# LED_Board.net
KiCad netlist of a schematic drawn in EAGLE
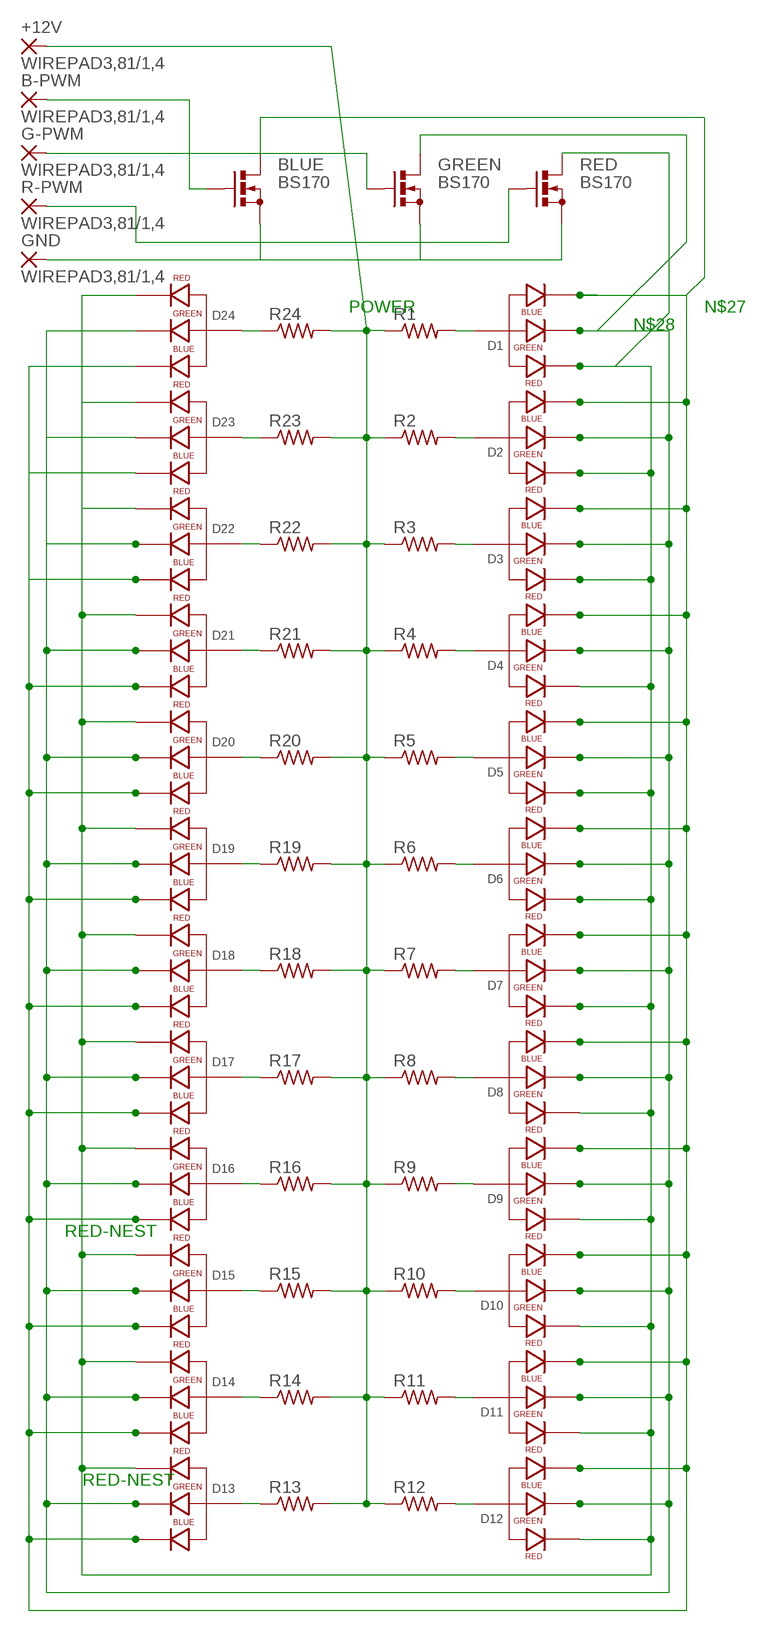
[diagram p0: schematic, sheet 1]

(export (version "E")
  (design (tool "Eeschema 10.0.6"))
  (components
    (comp (ref "+12V")
      (value "WIREPAD3,81/1,4")
      (footprint "eagle-import:3,81_1,4")
      (libsource (lib "eagle-import") (part "WIREPAD3,81/1,4"))
    )
    (comp (ref "B-PWM")
      (value "WIREPAD3,81/1,4")
      (footprint "eagle-import:3,81_1,4")
      (libsource (lib "eagle-import") (part "WIREPAD3,81/1,4"))
    )
    (comp (ref "BLUE")
      (value "BS170")
      (footprint "eagle-import:SOT54E")
      (libsource (lib "eagle-import") (part "BS170"))
    )
    (comp (ref "D1")
      (value "LED-RGB-CA-THRUCLEAR")
      (footprint "eagle-import:LED-RGB-THRU")
      (libsource (lib "eagle-import") (part "LED-RGB-CA-THRUCLEAR"))
    )
    (comp (ref "D2")
      (value "LED-RGB-CA-THRUCLEAR")
      (footprint "eagle-import:LED-RGB-THRU")
      (libsource (lib "eagle-import") (part "LED-RGB-CA-THRUCLEAR"))
    )
    (comp (ref "D3")
      (value "LED-RGB-CA-THRUCLEAR")
      (footprint "eagle-import:LED-RGB-THRU")
      (libsource (lib "eagle-import") (part "LED-RGB-CA-THRUCLEAR"))
    )
    (comp (ref "D4")
      (value "LED-RGB-CA-THRUCLEAR")
      (footprint "eagle-import:LED-RGB-THRU")
      (libsource (lib "eagle-import") (part "LED-RGB-CA-THRUCLEAR"))
    )
    (comp (ref "D5")
      (value "LED-RGB-CA-THRUCLEAR")
      (footprint "eagle-import:LED-RGB-THRU")
      (libsource (lib "eagle-import") (part "LED-RGB-CA-THRUCLEAR"))
    )
    (comp (ref "D6")
      (value "LED-RGB-CA-THRUCLEAR")
      (footprint "eagle-import:LED-RGB-THRU")
      (libsource (lib "eagle-import") (part "LED-RGB-CA-THRUCLEAR"))
    )
    (comp (ref "D7")
      (value "LED-RGB-CA-THRUCLEAR")
      (footprint "eagle-import:LED-RGB-THRU")
      (libsource (lib "eagle-import") (part "LED-RGB-CA-THRUCLEAR"))
    )
    (comp (ref "D8")
      (value "LED-RGB-CA-THRUCLEAR")
      (footprint "eagle-import:LED-RGB-THRU")
      (libsource (lib "eagle-import") (part "LED-RGB-CA-THRUCLEAR"))
    )
    (comp (ref "D9")
      (value "LED-RGB-CA-THRUCLEAR")
      (footprint "eagle-import:LED-RGB-THRU")
      (libsource (lib "eagle-import") (part "LED-RGB-CA-THRUCLEAR"))
    )
    (comp (ref "D10")
      (value "LED-RGB-CA-THRUCLEAR")
      (footprint "eagle-import:LED-RGB-THRU")
      (libsource (lib "eagle-import") (part "LED-RGB-CA-THRUCLEAR"))
    )
    (comp (ref "D11")
      (value "LED-RGB-CA-THRUCLEAR")
      (footprint "eagle-import:LED-RGB-THRU")
      (libsource (lib "eagle-import") (part "LED-RGB-CA-THRUCLEAR"))
    )
    (comp (ref "D12")
      (value "LED-RGB-CA-THRUCLEAR")
      (footprint "eagle-import:LED-RGB-THRU")
      (libsource (lib "eagle-import") (part "LED-RGB-CA-THRUCLEAR"))
    )
    (comp (ref "D13")
      (value "LED-RGB-CA-THRUCLEAR")
      (footprint "eagle-import:LED-RGB-THRU")
      (libsource (lib "eagle-import") (part "LED-RGB-CA-THRUCLEAR"))
    )
    (comp (ref "D14")
      (value "LED-RGB-CA-THRUCLEAR")
      (footprint "eagle-import:LED-RGB-THRU")
      (libsource (lib "eagle-import") (part "LED-RGB-CA-THRUCLEAR"))
    )
    (comp (ref "D15")
      (value "LED-RGB-CA-THRUCLEAR")
      (footprint "eagle-import:LED-RGB-THRU")
      (libsource (lib "eagle-import") (part "LED-RGB-CA-THRUCLEAR"))
    )
    (comp (ref "D16")
      (value "LED-RGB-CA-THRUCLEAR")
      (footprint "eagle-import:LED-RGB-THRU")
      (libsource (lib "eagle-import") (part "LED-RGB-CA-THRUCLEAR"))
    )
    (comp (ref "D17")
      (value "LED-RGB-CA-THRUCLEAR")
      (footprint "eagle-import:LED-RGB-THRU")
      (libsource (lib "eagle-import") (part "LED-RGB-CA-THRUCLEAR"))
    )
    (comp (ref "D18")
      (value "LED-RGB-CA-THRUCLEAR")
      (footprint "eagle-import:LED-RGB-THRU")
      (libsource (lib "eagle-import") (part "LED-RGB-CA-THRUCLEAR"))
    )
    (comp (ref "D19")
      (value "LED-RGB-CA-THRUCLEAR")
      (footprint "eagle-import:LED-RGB-THRU")
      (libsource (lib "eagle-import") (part "LED-RGB-CA-THRUCLEAR"))
    )
    (comp (ref "D20")
      (value "LED-RGB-CA-THRUCLEAR")
      (footprint "eagle-import:LED-RGB-THRU")
      (libsource (lib "eagle-import") (part "LED-RGB-CA-THRUCLEAR"))
    )
    (comp (ref "D21")
      (value "LED-RGB-CA-THRUCLEAR")
      (footprint "eagle-import:LED-RGB-THRU")
      (libsource (lib "eagle-import") (part "LED-RGB-CA-THRUCLEAR"))
    )
    (comp (ref "D22")
      (value "LED-RGB-CA-THRUCLEAR")
      (footprint "eagle-import:LED-RGB-THRU")
      (libsource (lib "eagle-import") (part "LED-RGB-CA-THRUCLEAR"))
    )
    (comp (ref "D23")
      (value "LED-RGB-CA-THRUCLEAR")
      (footprint "eagle-import:LED-RGB-THRU")
      (libsource (lib "eagle-import") (part "LED-RGB-CA-THRUCLEAR"))
    )
    (comp (ref "D24")
      (value "LED-RGB-CA-THRUCLEAR")
      (footprint "eagle-import:LED-RGB-THRU")
      (libsource (lib "eagle-import") (part "LED-RGB-CA-THRUCLEAR"))
    )
    (comp (ref "G-PWM")
      (value "WIREPAD3,81/1,4")
      (footprint "eagle-import:3,81_1,4")
      (libsource (lib "eagle-import") (part "WIREPAD3,81/1,4"))
    )
    (comp (ref "GND")
      (value "WIREPAD3,81/1,4")
      (footprint "eagle-import:3,81_1,4")
      (libsource (lib "eagle-import") (part "WIREPAD3,81/1,4"))
    )
    (comp (ref "GREEN")
      (value "BS170")
      (footprint "eagle-import:SOT54E")
      (libsource (lib "eagle-import") (part "BS170"))
    )
    (comp (ref "R-PWM")
      (value "WIREPAD3,81/1,4")
      (footprint "eagle-import:3,81_1,4")
      (libsource (lib "eagle-import") (part "WIREPAD3,81/1,4"))
    )
    (comp (ref "R1")
      (value "R-US_0207/10")
      (footprint "eagle-import:0207_10")
      (libsource (lib "eagle-import") (part "R-US_0207/10"))
    )
    (comp (ref "R2")
      (value "R-US_0207/10")
      (footprint "eagle-import:0207_10")
      (libsource (lib "eagle-import") (part "R-US_0207/10"))
    )
    (comp (ref "R3")
      (value "R-US_0207/10")
      (footprint "eagle-import:0207_10")
      (libsource (lib "eagle-import") (part "R-US_0207/10"))
    )
    (comp (ref "R4")
      (value "R-US_0207/10")
      (footprint "eagle-import:0207_10")
      (libsource (lib "eagle-import") (part "R-US_0207/10"))
    )
    (comp (ref "R5")
      (value "R-US_0207/10")
      (footprint "eagle-import:0207_10")
      (libsource (lib "eagle-import") (part "R-US_0207/10"))
    )
    (comp (ref "R6")
      (value "R-US_0207/10")
      (footprint "eagle-import:0207_10")
      (libsource (lib "eagle-import") (part "R-US_0207/10"))
    )
    (comp (ref "R7")
      (value "R-US_0207/10")
      (footprint "eagle-import:0207_10")
      (libsource (lib "eagle-import") (part "R-US_0207/10"))
    )
    (comp (ref "R8")
      (value "R-US_0207/10")
      (footprint "eagle-import:0207_10")
      (libsource (lib "eagle-import") (part "R-US_0207/10"))
    )
    (comp (ref "R9")
      (value "R-US_0207/10")
      (footprint "eagle-import:0207_10")
      (libsource (lib "eagle-import") (part "R-US_0207/10"))
    )
    (comp (ref "R10")
      (value "R-US_0207/10")
      (footprint "eagle-import:0207_10")
      (libsource (lib "eagle-import") (part "R-US_0207/10"))
    )
    (comp (ref "R11")
      (value "R-US_0207/10")
      (footprint "eagle-import:0207_10")
      (libsource (lib "eagle-import") (part "R-US_0207/10"))
    )
    (comp (ref "R12")
      (value "R-US_0207/10")
      (footprint "eagle-import:0207_10")
      (libsource (lib "eagle-import") (part "R-US_0207/10"))
    )
    (comp (ref "R13")
      (value "R-US_0207/10")
      (footprint "eagle-import:0207_10")
      (libsource (lib "eagle-import") (part "R-US_0207/10"))
    )
    (comp (ref "R14")
      (value "R-US_0207/10")
      (footprint "eagle-import:0207_10")
      (libsource (lib "eagle-import") (part "R-US_0207/10"))
    )
    (comp (ref "R15")
      (value "R-US_0207/10")
      (footprint "eagle-import:0207_10")
      (libsource (lib "eagle-import") (part "R-US_0207/10"))
    )
    (comp (ref "R16")
      (value "R-US_0207/10")
      (footprint "eagle-import:0207_10")
      (libsource (lib "eagle-import") (part "R-US_0207/10"))
    )
    (comp (ref "R17")
      (value "R-US_0207/10")
      (footprint "eagle-import:0207_10")
      (libsource (lib "eagle-import") (part "R-US_0207/10"))
    )
    (comp (ref "R18")
      (value "R-US_0207/10")
      (footprint "eagle-import:0207_10")
      (libsource (lib "eagle-import") (part "R-US_0207/10"))
    )
    (comp (ref "R19")
      (value "R-US_0207/10")
      (footprint "eagle-import:0207_10")
      (libsource (lib "eagle-import") (part "R-US_0207/10"))
    )
    (comp (ref "R20")
      (value "R-US_0207/10")
      (footprint "eagle-import:0207_10")
      (libsource (lib "eagle-import") (part "R-US_0207/10"))
    )
    (comp (ref "R21")
      (value "R-US_0207/10")
      (footprint "eagle-import:0207_10")
      (libsource (lib "eagle-import") (part "R-US_0207/10"))
    )
    (comp (ref "R22")
      (value "R-US_0207/10")
      (footprint "eagle-import:0207_10")
      (libsource (lib "eagle-import") (part "R-US_0207/10"))
    )
    (comp (ref "R23")
      (value "R-US_0207/10")
      (footprint "eagle-import:0207_10")
      (libsource (lib "eagle-import") (part "R-US_0207/10"))
    )
    (comp (ref "R24")
      (value "R-US_0207/10")
      (footprint "eagle-import:0207_10")
      (libsource (lib "eagle-import") (part "R-US_0207/10"))
    )
    (comp (ref "RED")
      (value "BS170")
      (footprint "eagle-import:SOT54E")
      (libsource (lib "eagle-import") (part "BS170"))
    )
  )
  (nets
    (net (code "1") (name "/N$27") (class "Default")
      (node (ref "BLUE") (pin "D") (pinfunction "D_D") (pintype "passive"))
      (node (ref "D1") (pin "4") (pinfunction "BLUE_CATHODE_4") (pintype "bidirectional"))
      (node (ref "D10") (pin "4") (pinfunction "BLUE_CATHODE_4") (pintype "bidirectional"))
      (node (ref "D11") (pin "4") (pinfunction "BLUE_CATHODE_4") (pintype "bidirectional"))
      (node (ref "D12") (pin "4") (pinfunction "BLUE_CATHODE_4") (pintype "bidirectional"))
      (node (ref "D13") (pin "4") (pinfunction "BLUE_CATHODE_4") (pintype "bidirectional"))
      (node (ref "D14") (pin "4") (pinfunction "BLUE_CATHODE_4") (pintype "bidirectional"))
      (node (ref "D15") (pin "4") (pinfunction "BLUE_CATHODE_4") (pintype "bidirectional"))
      (node (ref "D16") (pin "4") (pinfunction "BLUE_CATHODE_4") (pintype "bidirectional"))
      (node (ref "D17") (pin "4") (pinfunction "BLUE_CATHODE_4") (pintype "bidirectional"))
      (node (ref "D18") (pin "4") (pinfunction "BLUE_CATHODE_4") (pintype "bidirectional"))
      (node (ref "D19") (pin "4") (pinfunction "BLUE_CATHODE_4") (pintype "bidirectional"))
      (node (ref "D2") (pin "4") (pinfunction "BLUE_CATHODE_4") (pintype "bidirectional"))
      (node (ref "D20") (pin "4") (pinfunction "BLUE_CATHODE_4") (pintype "bidirectional"))
      (node (ref "D21") (pin "4") (pinfunction "BLUE_CATHODE_4") (pintype "bidirectional"))
      (node (ref "D22") (pin "4") (pinfunction "BLUE_CATHODE_4") (pintype "bidirectional"))
      (node (ref "D23") (pin "4") (pinfunction "BLUE_CATHODE_4") (pintype "bidirectional"))
      (node (ref "D24") (pin "4") (pinfunction "BLUE_CATHODE_4") (pintype "bidirectional"))
      (node (ref "D3") (pin "4") (pinfunction "BLUE_CATHODE_4") (pintype "bidirectional"))
      (node (ref "D4") (pin "4") (pinfunction "BLUE_CATHODE_4") (pintype "bidirectional"))
      (node (ref "D5") (pin "4") (pinfunction "BLUE_CATHODE_4") (pintype "bidirectional"))
      (node (ref "D6") (pin "4") (pinfunction "BLUE_CATHODE_4") (pintype "bidirectional"))
      (node (ref "D7") (pin "4") (pinfunction "BLUE_CATHODE_4") (pintype "bidirectional"))
      (node (ref "D8") (pin "4") (pinfunction "BLUE_CATHODE_4") (pintype "bidirectional"))
      (node (ref "D9") (pin "4") (pinfunction "BLUE_CATHODE_4") (pintype "bidirectional"))
    )
    (net (code "2") (name "/N$28") (class "Default")
      (node (ref "D1") (pin "3") (pinfunction "GREEN_CATHODE_3") (pintype "bidirectional"))
      (node (ref "D10") (pin "3") (pinfunction "GREEN_CATHODE_3") (pintype "bidirectional"))
      (node (ref "D11") (pin "3") (pinfunction "GREEN_CATHODE_3") (pintype "bidirectional"))
      (node (ref "D12") (pin "3") (pinfunction "GREEN_CATHODE_3") (pintype "bidirectional"))
      (node (ref "D13") (pin "3") (pinfunction "GREEN_CATHODE_3") (pintype "bidirectional"))
      (node (ref "D14") (pin "3") (pinfunction "GREEN_CATHODE_3") (pintype "bidirectional"))
      (node (ref "D15") (pin "3") (pinfunction "GREEN_CATHODE_3") (pintype "bidirectional"))
      (node (ref "D16") (pin "3") (pinfunction "GREEN_CATHODE_3") (pintype "bidirectional"))
      (node (ref "D17") (pin "3") (pinfunction "GREEN_CATHODE_3") (pintype "bidirectional"))
      (node (ref "D18") (pin "3") (pinfunction "GREEN_CATHODE_3") (pintype "bidirectional"))
      (node (ref "D19") (pin "3") (pinfunction "GREEN_CATHODE_3") (pintype "bidirectional"))
      (node (ref "D2") (pin "3") (pinfunction "GREEN_CATHODE_3") (pintype "bidirectional"))
      (node (ref "D20") (pin "3") (pinfunction "GREEN_CATHODE_3") (pintype "bidirectional"))
      (node (ref "D21") (pin "3") (pinfunction "GREEN_CATHODE_3") (pintype "bidirectional"))
      (node (ref "D22") (pin "3") (pinfunction "GREEN_CATHODE_3") (pintype "bidirectional"))
      (node (ref "D23") (pin "3") (pinfunction "GREEN_CATHODE_3") (pintype "bidirectional"))
      (node (ref "D24") (pin "3") (pinfunction "GREEN_CATHODE_3") (pintype "bidirectional"))
      (node (ref "D3") (pin "3") (pinfunction "GREEN_CATHODE_3") (pintype "bidirectional"))
      (node (ref "D4") (pin "3") (pinfunction "GREEN_CATHODE_3") (pintype "bidirectional"))
      (node (ref "D5") (pin "3") (pinfunction "GREEN_CATHODE_3") (pintype "bidirectional"))
      (node (ref "D6") (pin "3") (pinfunction "GREEN_CATHODE_3") (pintype "bidirectional"))
      (node (ref "D7") (pin "3") (pinfunction "GREEN_CATHODE_3") (pintype "bidirectional"))
      (node (ref "D8") (pin "3") (pinfunction "GREEN_CATHODE_3") (pintype "bidirectional"))
      (node (ref "D9") (pin "3") (pinfunction "GREEN_CATHODE_3") (pintype "bidirectional"))
      (node (ref "GREEN") (pin "D") (pinfunction "D_D") (pintype "passive"))
    )
    (net (code "3") (name "/POWER") (class "Default")
      (node (ref "+12V") (pin "1") (pinfunction "P_1") (pintype "passive"))
      (node (ref "R1") (pin "1") (pinfunction "1_1") (pintype "passive"))
      (node (ref "R10") (pin "1") (pinfunction "1_1") (pintype "passive"))
      (node (ref "R11") (pin "1") (pinfunction "1_1") (pintype "passive"))
      (node (ref "R12") (pin "1") (pinfunction "1_1") (pintype "passive"))
      (node (ref "R13") (pin "2") (pinfunction "2_2") (pintype "passive"))
      (node (ref "R14") (pin "2") (pinfunction "2_2") (pintype "passive"))
      (node (ref "R15") (pin "2") (pinfunction "2_2") (pintype "passive"))
      (node (ref "R16") (pin "2") (pinfunction "2_2") (pintype "passive"))
      (node (ref "R17") (pin "2") (pinfunction "2_2") (pintype "passive"))
      (node (ref "R18") (pin "2") (pinfunction "2_2") (pintype "passive"))
      (node (ref "R19") (pin "2") (pinfunction "2_2") (pintype "passive"))
      (node (ref "R2") (pin "1") (pinfunction "1_1") (pintype "passive"))
      (node (ref "R20") (pin "2") (pinfunction "2_2") (pintype "passive"))
      (node (ref "R21") (pin "2") (pinfunction "2_2") (pintype "passive"))
      (node (ref "R22") (pin "2") (pinfunction "2_2") (pintype "passive"))
      (node (ref "R23") (pin "2") (pinfunction "2_2") (pintype "passive"))
      (node (ref "R24") (pin "2") (pinfunction "2_2") (pintype "passive"))
      (node (ref "R3") (pin "1") (pinfunction "1_1") (pintype "passive"))
      (node (ref "R4") (pin "1") (pinfunction "1_1") (pintype "passive"))
      (node (ref "R5") (pin "1") (pinfunction "1_1") (pintype "passive"))
      (node (ref "R6") (pin "1") (pinfunction "1_1") (pintype "passive"))
      (node (ref "R7") (pin "1") (pinfunction "1_1") (pintype "passive"))
      (node (ref "R8") (pin "1") (pinfunction "1_1") (pintype "passive"))
      (node (ref "R9") (pin "1") (pinfunction "1_1") (pintype "passive"))
    )
    (net (code "4") (name "/RED-NEST") (class "Default")
      (node (ref "D1") (pin "1") (pinfunction "RED_CATHODE_1") (pintype "bidirectional"))
      (node (ref "D10") (pin "1") (pinfunction "RED_CATHODE_1") (pintype "bidirectional"))
      (node (ref "D11") (pin "1") (pinfunction "RED_CATHODE_1") (pintype "bidirectional"))
      (node (ref "D12") (pin "1") (pinfunction "RED_CATHODE_1") (pintype "bidirectional"))
      (node (ref "D13") (pin "1") (pinfunction "RED_CATHODE_1") (pintype "bidirectional"))
      (node (ref "D14") (pin "1") (pinfunction "RED_CATHODE_1") (pintype "bidirectional"))
      (node (ref "D15") (pin "1") (pinfunction "RED_CATHODE_1") (pintype "bidirectional"))
      (node (ref "D16") (pin "1") (pinfunction "RED_CATHODE_1") (pintype "bidirectional"))
      (node (ref "D17") (pin "1") (pinfunction "RED_CATHODE_1") (pintype "bidirectional"))
      (node (ref "D18") (pin "1") (pinfunction "RED_CATHODE_1") (pintype "bidirectional"))
      (node (ref "D19") (pin "1") (pinfunction "RED_CATHODE_1") (pintype "bidirectional"))
      (node (ref "D2") (pin "1") (pinfunction "RED_CATHODE_1") (pintype "bidirectional"))
      (node (ref "D20") (pin "1") (pinfunction "RED_CATHODE_1") (pintype "bidirectional"))
      (node (ref "D21") (pin "1") (pinfunction "RED_CATHODE_1") (pintype "bidirectional"))
      (node (ref "D22") (pin "1") (pinfunction "RED_CATHODE_1") (pintype "bidirectional"))
      (node (ref "D23") (pin "1") (pinfunction "RED_CATHODE_1") (pintype "bidirectional"))
      (node (ref "D24") (pin "1") (pinfunction "RED_CATHODE_1") (pintype "bidirectional"))
      (node (ref "D3") (pin "1") (pinfunction "RED_CATHODE_1") (pintype "bidirectional"))
      (node (ref "D4") (pin "1") (pinfunction "RED_CATHODE_1") (pintype "bidirectional"))
      (node (ref "D5") (pin "1") (pinfunction "RED_CATHODE_1") (pintype "bidirectional"))
      (node (ref "D6") (pin "1") (pinfunction "RED_CATHODE_1") (pintype "bidirectional"))
      (node (ref "D7") (pin "1") (pinfunction "RED_CATHODE_1") (pintype "bidirectional"))
      (node (ref "D8") (pin "1") (pinfunction "RED_CATHODE_1") (pintype "bidirectional"))
      (node (ref "D9") (pin "1") (pinfunction "RED_CATHODE_1") (pintype "bidirectional"))
      (node (ref "RED") (pin "D") (pinfunction "D_D") (pintype "passive"))
    )
    (net (code "5") (name "Net-(B-PWM-P)") (class "Default")
      (node (ref "B-PWM") (pin "1") (pinfunction "P_1") (pintype "passive"))
      (node (ref "BLUE") (pin "G") (pinfunction "G_G") (pintype "passive"))
    )
    (net (code "6") (name "Net-(D1-ANODE)") (class "Default")
      (node (ref "D1") (pin "2") (pinfunction "ANODE_2") (pintype "bidirectional"))
      (node (ref "R1") (pin "2") (pinfunction "2_2") (pintype "passive"))
    )
    (net (code "7") (name "Net-(D2-ANODE)") (class "Default")
      (node (ref "D2") (pin "2") (pinfunction "ANODE_2") (pintype "bidirectional"))
      (node (ref "R2") (pin "2") (pinfunction "2_2") (pintype "passive"))
    )
    (net (code "8") (name "Net-(D3-ANODE)") (class "Default")
      (node (ref "D3") (pin "2") (pinfunction "ANODE_2") (pintype "bidirectional"))
      (node (ref "R3") (pin "2") (pinfunction "2_2") (pintype "passive"))
    )
    (net (code "9") (name "Net-(D4-ANODE)") (class "Default")
      (node (ref "D4") (pin "2") (pinfunction "ANODE_2") (pintype "bidirectional"))
      (node (ref "R4") (pin "2") (pinfunction "2_2") (pintype "passive"))
    )
    (net (code "10") (name "Net-(D5-ANODE)") (class "Default")
      (node (ref "D5") (pin "2") (pinfunction "ANODE_2") (pintype "bidirectional"))
      (node (ref "R5") (pin "2") (pinfunction "2_2") (pintype "passive"))
    )
    (net (code "11") (name "Net-(D6-ANODE)") (class "Default")
      (node (ref "D6") (pin "2") (pinfunction "ANODE_2") (pintype "bidirectional"))
      (node (ref "R6") (pin "2") (pinfunction "2_2") (pintype "passive"))
    )
    (net (code "12") (name "Net-(D7-ANODE)") (class "Default")
      (node (ref "D7") (pin "2") (pinfunction "ANODE_2") (pintype "bidirectional"))
      (node (ref "R7") (pin "2") (pinfunction "2_2") (pintype "passive"))
    )
    (net (code "13") (name "Net-(D8-ANODE)") (class "Default")
      (node (ref "D8") (pin "2") (pinfunction "ANODE_2") (pintype "bidirectional"))
      (node (ref "R8") (pin "2") (pinfunction "2_2") (pintype "passive"))
    )
    (net (code "14") (name "Net-(D9-ANODE)") (class "Default")
      (node (ref "D9") (pin "2") (pinfunction "ANODE_2") (pintype "bidirectional"))
      (node (ref "R9") (pin "2") (pinfunction "2_2") (pintype "passive"))
    )
    (net (code "15") (name "Net-(D10-ANODE)") (class "Default")
      (node (ref "D10") (pin "2") (pinfunction "ANODE_2") (pintype "bidirectional"))
      (node (ref "R10") (pin "2") (pinfunction "2_2") (pintype "passive"))
    )
    (net (code "16") (name "Net-(D11-ANODE)") (class "Default")
      (node (ref "D11") (pin "2") (pinfunction "ANODE_2") (pintype "bidirectional"))
      (node (ref "R11") (pin "2") (pinfunction "2_2") (pintype "passive"))
    )
    (net (code "17") (name "Net-(D12-ANODE)") (class "Default")
      (node (ref "D12") (pin "2") (pinfunction "ANODE_2") (pintype "bidirectional"))
      (node (ref "R12") (pin "2") (pinfunction "2_2") (pintype "passive"))
    )
    (net (code "18") (name "Net-(D13-ANODE)") (class "Default")
      (node (ref "D13") (pin "2") (pinfunction "ANODE_2") (pintype "bidirectional"))
      (node (ref "R13") (pin "1") (pinfunction "1_1") (pintype "passive"))
    )
    (net (code "19") (name "Net-(D14-ANODE)") (class "Default")
      (node (ref "D14") (pin "2") (pinfunction "ANODE_2") (pintype "bidirectional"))
      (node (ref "R14") (pin "1") (pinfunction "1_1") (pintype "passive"))
    )
    (net (code "20") (name "Net-(D15-ANODE)") (class "Default")
      (node (ref "D15") (pin "2") (pinfunction "ANODE_2") (pintype "bidirectional"))
      (node (ref "R15") (pin "1") (pinfunction "1_1") (pintype "passive"))
    )
    (net (code "21") (name "Net-(D16-ANODE)") (class "Default")
      (node (ref "D16") (pin "2") (pinfunction "ANODE_2") (pintype "bidirectional"))
      (node (ref "R16") (pin "1") (pinfunction "1_1") (pintype "passive"))
    )
    (net (code "22") (name "Net-(D17-ANODE)") (class "Default")
      (node (ref "D17") (pin "2") (pinfunction "ANODE_2") (pintype "bidirectional"))
      (node (ref "R17") (pin "1") (pinfunction "1_1") (pintype "passive"))
    )
    (net (code "23") (name "Net-(D18-ANODE)") (class "Default")
      (node (ref "D18") (pin "2") (pinfunction "ANODE_2") (pintype "bidirectional"))
      (node (ref "R18") (pin "1") (pinfunction "1_1") (pintype "passive"))
    )
    (net (code "24") (name "Net-(D19-ANODE)") (class "Default")
      (node (ref "D19") (pin "2") (pinfunction "ANODE_2") (pintype "bidirectional"))
      (node (ref "R19") (pin "1") (pinfunction "1_1") (pintype "passive"))
    )
    (net (code "25") (name "Net-(D20-ANODE)") (class "Default")
      (node (ref "D20") (pin "2") (pinfunction "ANODE_2") (pintype "bidirectional"))
      (node (ref "R20") (pin "1") (pinfunction "1_1") (pintype "passive"))
    )
    (net (code "26") (name "Net-(D21-ANODE)") (class "Default")
      (node (ref "D21") (pin "2") (pinfunction "ANODE_2") (pintype "bidirectional"))
      (node (ref "R21") (pin "1") (pinfunction "1_1") (pintype "passive"))
    )
    (net (code "27") (name "Net-(D22-ANODE)") (class "Default")
      (node (ref "D22") (pin "2") (pinfunction "ANODE_2") (pintype "bidirectional"))
      (node (ref "R22") (pin "1") (pinfunction "1_1") (pintype "passive"))
    )
    (net (code "28") (name "Net-(D23-ANODE)") (class "Default")
      (node (ref "D23") (pin "2") (pinfunction "ANODE_2") (pintype "bidirectional"))
      (node (ref "R23") (pin "1") (pinfunction "1_1") (pintype "passive"))
    )
    (net (code "29") (name "Net-(D24-ANODE)") (class "Default")
      (node (ref "D24") (pin "2") (pinfunction "ANODE_2") (pintype "bidirectional"))
      (node (ref "R24") (pin "1") (pinfunction "1_1") (pintype "passive"))
    )
    (net (code "30") (name "Net-(G-PWM-P)") (class "Default")
      (node (ref "G-PWM") (pin "1") (pinfunction "P_1") (pintype "passive"))
      (node (ref "GREEN") (pin "G") (pinfunction "G_G") (pintype "passive"))
    )
    (net (code "31") (name "Net-(GND-P)") (class "Default")
      (node (ref "BLUE") (pin "S") (pinfunction "S_S") (pintype "passive"))
      (node (ref "GND") (pin "1") (pinfunction "P_1") (pintype "passive"))
      (node (ref "GREEN") (pin "S") (pinfunction "S_S") (pintype "passive"))
      (node (ref "RED") (pin "S") (pinfunction "S_S") (pintype "passive"))
    )
    (net (code "32") (name "Net-(R-PWM-P)") (class "Default")
      (node (ref "R-PWM") (pin "1") (pinfunction "P_1") (pintype "passive"))
      (node (ref "RED") (pin "G") (pinfunction "G_G") (pintype "passive"))
    )
  )
)
